# IoT_pro_01.net
KiCad netlist of a schematic drawn in EAGLE
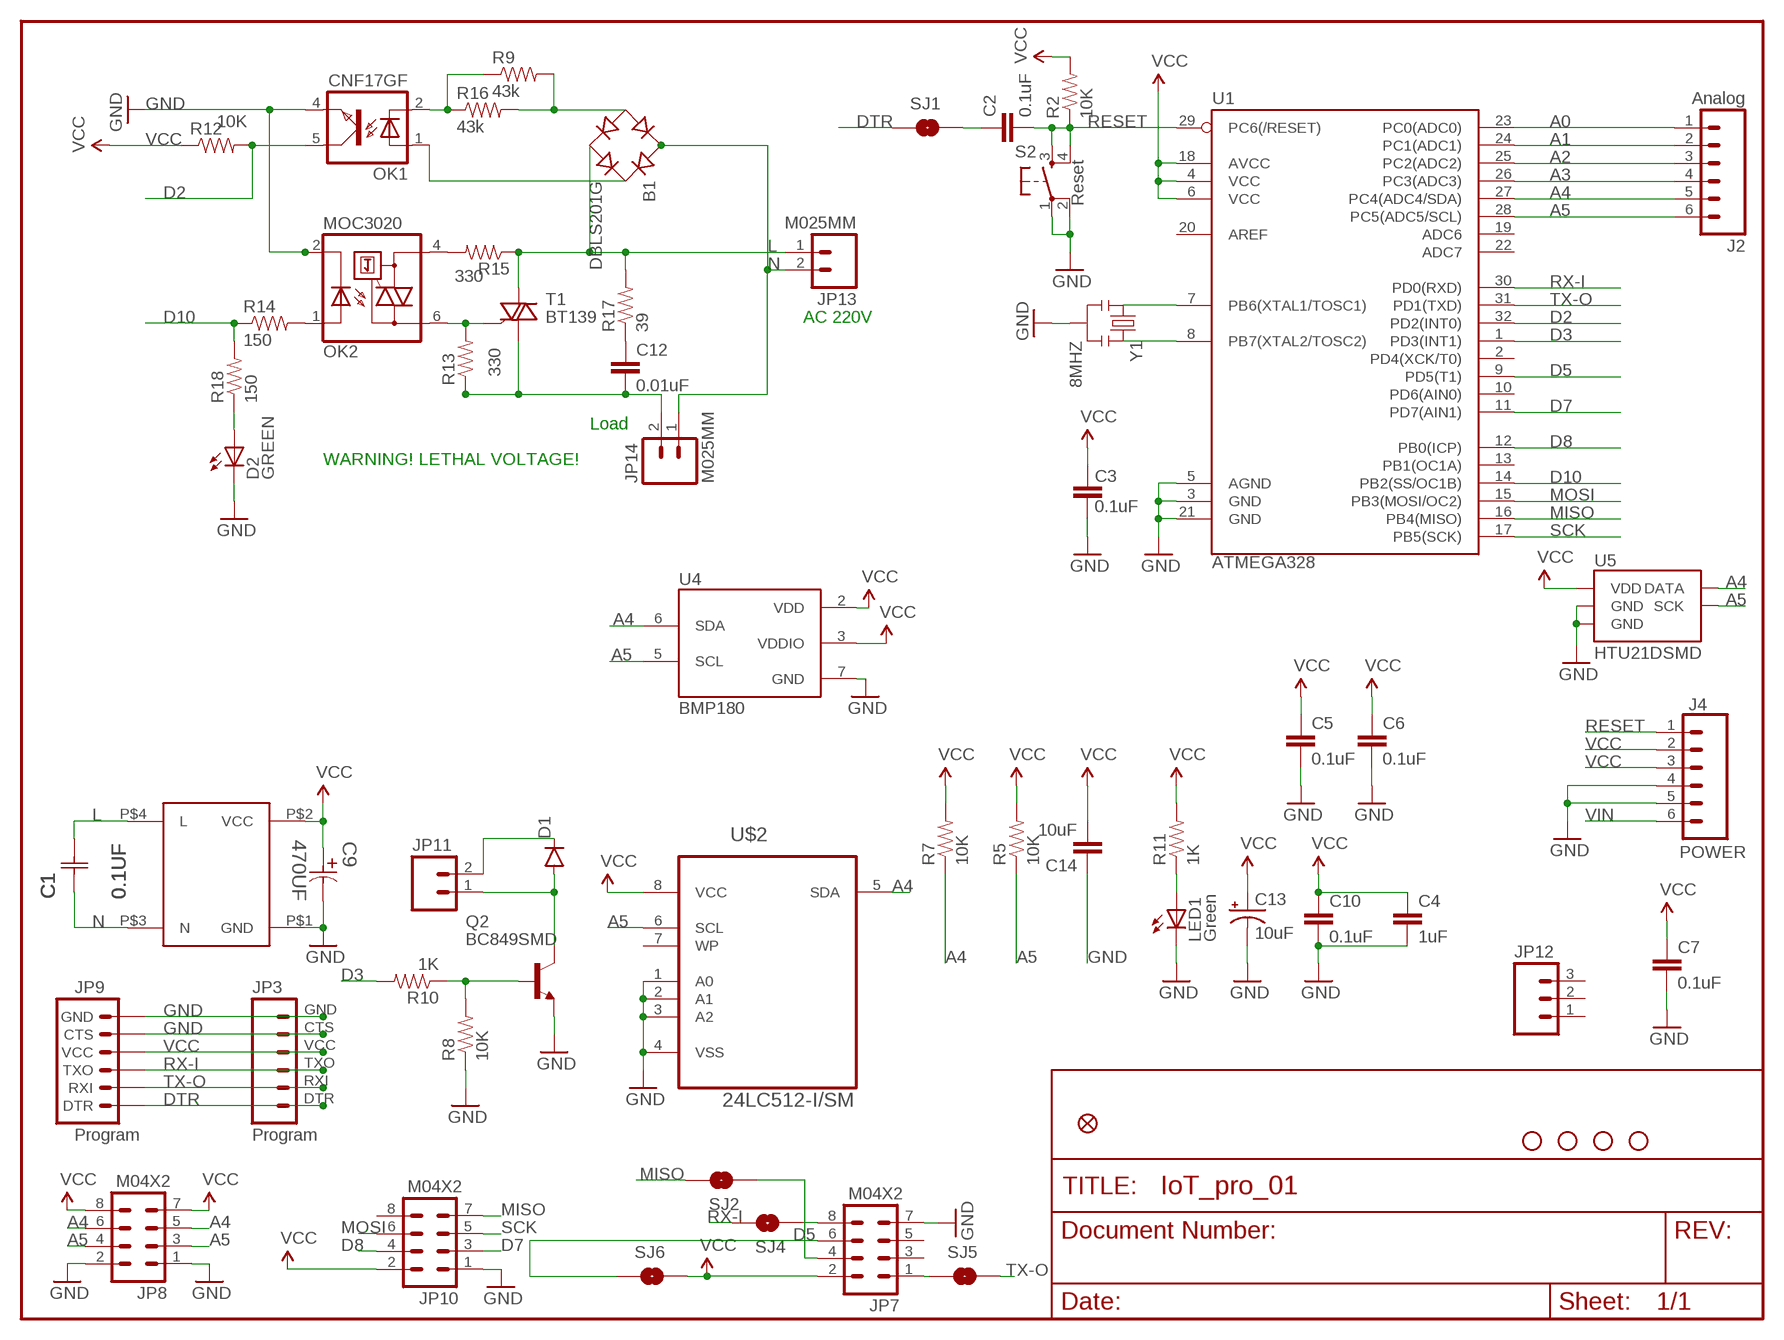
[diagram p0: schematic, sheet 1]

(export (version "E")
  (design (tool "Eeschema 10.0.6"))
  (components
    (comp (ref "B1")
      (value "DBLS201G")
      (footprint "eagle-import:DBS")
      (libsource (lib "eagle-import") (part "DB?GLS201"))
    )
    (comp (ref "C1")
      (value "0.1UF")
      (footprint "eagle-import:CAPM1750X500X1250")
      (fields (field (name "MPN") "ECQUAAF104M") (field (name "TOLERANCE") "±20%"))
      (libsource (lib "eagle-import") (part "ECQ-L17.5-T5UAAF104M"))
    )
    (comp (ref "C2")
      (value "0.1uF")
      (footprint "eagle-import:0805")
      (libsource (lib "eagle-import") (part "CAP0805"))
    )
    (comp (ref "C3")
      (value "0.1uF")
      (footprint "eagle-import:0805")
      (libsource (lib "eagle-import") (part "CAP0805"))
    )
    (comp (ref "C4")
      (value "1uF")
      (footprint "eagle-import:0805")
      (libsource (lib "eagle-import") (part "CAP0805"))
    )
    (comp (ref "C5")
      (value "0.1uF")
      (footprint "eagle-import:0805")
      (libsource (lib "eagle-import") (part "CAP0805"))
    )
    (comp (ref "C6")
      (value "0.1uF")
      (footprint "eagle-import:0805")
      (libsource (lib "eagle-import") (part "CAP0805"))
    )
    (comp (ref "C7")
      (value "0.1uF")
      (footprint "eagle-import:0805")
      (libsource (lib "eagle-import") (part "CAP0805"))
    )
    (comp (ref "C9")
      (value "470UF")
      (footprint "eagle-import:CAPAE660X800N")
      (fields (field (name "MPN") "EEE-FTA471XAP") (field (name "TOLERANCE") "±20 %"))
      (libsource (lib "eagle-import") (part "EEE--CASE-D8FTA471XAP"))
    )
    (comp (ref "C10")
      (value "0.1uF")
      (footprint "eagle-import:0805")
      (libsource (lib "eagle-import") (part "CAP0805"))
    )
    (comp (ref "C12")
      (value "0.01uF")
      (footprint "eagle-import:C1206")
      (libsource (lib "eagle-import") (part "C-EUC1206"))
    )
    (comp (ref "C13")
      (value "10uF")
      (footprint "eagle-import:EIA3216")
      (libsource (lib "eagle-import") (part "CAP_POL1206"))
    )
    (comp (ref "C14")
      (value "10uF")
      (footprint "eagle-import:1206")
      (libsource (lib "eagle-import") (part "SparkFun-Capacitors_CAP1206"))
    )
    (comp (ref "D1")
      (value "DIODESOD")
      (footprint "eagle-import:SOD-323")
      (libsource (lib "eagle-import") (part "DIODESOD"))
    )
    (comp (ref "D2")
      (value "GREEN")
      (footprint "eagle-import:PLCC2")
      (libsource (lib "eagle-import") (part "_T679-?-1E1F1LG"))
    )
    (comp (ref "J2")
      (value "Analog")
      (footprint "eagle-import:1X06")
      (libsource (lib "eagle-import") (part "M06SIP"))
    )
    (comp (ref "J4")
      (value "POWER")
      (footprint "eagle-import:1X06")
      (libsource (lib "eagle-import") (part "M06SIP"))
    )
    (comp (ref "JP2")
      (value "FIDUCIAL1X2.5")
      (footprint "eagle-import:FIDUCIAL-1X2.5")
      (libsource (lib "eagle-import") (part "FIDUCIAL1X2.5"))
    )
    (comp (ref "JP3")
      (value "Program")
      (footprint "eagle-import:1X06")
      (libsource (lib "eagle-import") (part "SparkFun-Connectors_M06SIP"))
    )
    (comp (ref "JP7")
      (value "M04X2")
      (footprint "eagle-import:2X4")
      (libsource (lib "eagle-import") (part "M04X2"))
    )
    (comp (ref "JP8")
      (value "M04X2")
      (footprint "eagle-import:2X4")
      (libsource (lib "eagle-import") (part "M04X2"))
    )
    (comp (ref "JP9")
      (value "Program")
      (footprint "eagle-import:1X06-SMD")
      (libsource (lib "eagle-import") (part "ARDUINO_SERIAL_PROGRAMSMD"))
    )
    (comp (ref "JP10")
      (value "M04X2")
      (footprint "eagle-import:2X4")
      (libsource (lib "eagle-import") (part "M04X2"))
    )
    (comp (ref "JP11")
      (value "M02PTH")
      (footprint "eagle-import:1X02")
      (libsource (lib "eagle-import") (part "M02PTH"))
    )
    (comp (ref "JP12")
      (value "M03PTH")
      (footprint "eagle-import:1X03")
      (libsource (lib "eagle-import") (part "M03PTH"))
    )
    (comp (ref "JP13")
      (value "M025MM")
      (footprint "eagle-import:SCREWTERMINAL-5MM-2")
      (libsource (lib "eagle-import") (part "M025MM"))
    )
    (comp (ref "JP14")
      (value "M025MM")
      (footprint "eagle-import:SCREWTERMINAL-5MM-2")
      (libsource (lib "eagle-import") (part "M025MM"))
    )
    (comp (ref "LED1")
      (value "Green")
      (footprint "eagle-import:PLCC2")
      (libsource (lib "eagle-import") (part "_T679-?-1E1F1LG"))
    )
    (comp (ref "OK1")
      (value "CNF17GF")
      (footprint "eagle-import:DIL06B")
      (libsource (lib "eagle-import") (part "CNF17GF"))
    )
    (comp (ref "OK2")
      (value "MOC3020")
      (footprint "eagle-import:DIL6-SMD")
      (fields (field (name "MF") "FAIRCHILD SEMICONDUCTOR") (field (name "MPN") "MOC3031SM"))
      (libsource (lib "eagle-import") (part "MOC30S31"))
    )
    (comp (ref "Q2")
      (value "BC849SMD")
      (footprint "eagle-import:SOT23-BEC")
      (libsource (lib "eagle-import") (part "BC849SMD"))
    )
    (comp (ref "R2")
      (value "10K")
      (footprint "eagle-import:0805")
      (libsource (lib "eagle-import") (part "RESISTOR0805-RES"))
    )
    (comp (ref "R5")
      (value "10K")
      (footprint "eagle-import:0805")
      (libsource (lib "eagle-import") (part "RESISTOR0805-RES"))
    )
    (comp (ref "R7")
      (value "10K")
      (footprint "eagle-import:0805")
      (libsource (lib "eagle-import") (part "RESISTOR0805-RES"))
    )
    (comp (ref "R8")
      (value "10K")
      (footprint "eagle-import:0805")
      (libsource (lib "eagle-import") (part "RESISTOR0805-RES"))
    )
    (comp (ref "R9")
      (value "43k")
      (footprint "eagle-import:1206")
      (fields (field (name "K") "45K"))
      (libsource (lib "eagle-import") (part "SparkFun-Resistors_RESISTOR1206"))
    )
    (comp (ref "R10")
      (value "1K")
      (footprint "eagle-import:0805")
      (libsource (lib "eagle-import") (part "RESISTOR0805-RES"))
    )
    (comp (ref "R11")
      (value "1K")
      (footprint "eagle-import:0805")
      (libsource (lib "eagle-import") (part "RESISTOR0805-RES"))
    )
    (comp (ref "R12")
      (value "RESISTOR0805-RES")
      (footprint "eagle-import:0805")
      (fields (field (name "OHM") "10K"))
      (libsource (lib "eagle-import") (part "SparkFun-Resistors_RESISTOR0805-RES"))
    )
    (comp (ref "R13")
      (value "RESISTOR1206")
      (footprint "eagle-import:1206")
      (fields (field (name "OHM") "330"))
      (libsource (lib "eagle-import") (part "SparkFun-Resistors_RESISTOR1206"))
    )
    (comp (ref "R14")
      (value "150")
      (footprint "eagle-import:0805")
      (fields (field (name "OHM") "330"))
      (libsource (lib "eagle-import") (part "SparkFun-Resistors_RESISTOR0805-RES"))
    )
    (comp (ref "R15")
      (value "RESISTOR1206")
      (footprint "eagle-import:1206")
      (fields (field (name "OHM") "330"))
      (libsource (lib "eagle-import") (part "SparkFun-Resistors_RESISTOR1206"))
    )
    (comp (ref "R16")
      (value "43k")
      (footprint "eagle-import:1206")
      (fields (field (name "K") "45K"))
      (libsource (lib "eagle-import") (part "SparkFun-Resistors_RESISTOR1206"))
    )
    (comp (ref "R17")
      (value "39")
      (footprint "eagle-import:1206")
      (fields (field (name "K") "45K"))
      (libsource (lib "eagle-import") (part "SparkFun-Resistors_RESISTOR1206"))
    )
    (comp (ref "R18")
      (value "150")
      (footprint "eagle-import:0805")
      (fields (field (name "OHM") "330"))
      (libsource (lib "eagle-import") (part "SparkFun-Resistors_RESISTOR0805-RES"))
    )
    (comp (ref "S2")
      (value "Reset")
      (footprint "eagle-import:TACTILE_SWITCH_SMD")
      (libsource (lib "eagle-import") (part "TAC_SWITCHSMD"))
    )
    (comp (ref "SJ1")
      (value "SOLDERJUMPERNC2")
      (footprint "eagle-import:SJ_2S-NOTRACE")
      (libsource (lib "eagle-import") (part "SOLDERJUMPERNC2"))
    )
    (comp (ref "SJ2")
      (value "SOLDERJUMPERNC2")
      (footprint "eagle-import:SJ_2S-NOTRACE")
      (libsource (lib "eagle-import") (part "SOLDERJUMPERNC2"))
    )
    (comp (ref "SJ4")
      (value "SOLDERJUMPERNC2")
      (footprint "eagle-import:SJ_2S-NOTRACE")
      (libsource (lib "eagle-import") (part "SOLDERJUMPERNC2"))
    )
    (comp (ref "SJ5")
      (value "SOLDERJUMPERNC2")
      (footprint "eagle-import:SJ_2S-NOTRACE")
      (libsource (lib "eagle-import") (part "SOLDERJUMPERNC2"))
    )
    (comp (ref "SJ6")
      (value "SOLDERJUMPERNC2")
      (footprint "eagle-import:SJ_2S-NOTRACE")
      (libsource (lib "eagle-import") (part "SOLDERJUMPERNC2"))
    )
    (comp (ref "T1")
      (value "BT139")
      (footprint "eagle-import:TO220AB")
      (libsource (lib "eagle-import") (part "BT136"))
    )
    (comp (ref "U$1")
      (value "STAND-OFFTIGHT")
      (footprint "eagle-import:STAND-OFF-TIGHT")
      (libsource (lib "eagle-import") (part "STAND-OFFTIGHT"))
    )
    (comp (ref "U$2")
      (value "24LC512-I/SM")
      (footprint "eagle-import:SOIC127P794X203-8N")
      (libsource (lib "eagle-import") (part "24LC512-I/SM"))
    )
    (comp (ref "U$3")
      (value "STAND-OFFTIGHT")
      (footprint "eagle-import:STAND-OFF-TIGHT")
      (libsource (lib "eagle-import") (part "STAND-OFFTIGHT"))
    )
    (comp (ref "U$4")
      (value "AC-DCCON")
      (footprint "eagle-import:VTX-214-001-103")
      (libsource (lib "eagle-import") (part "AC-DCCON"))
    )
    (comp (ref "U$9")
      (value "STAND-OFFTIGHT")
      (footprint "eagle-import:STAND-OFF-TIGHT")
      (libsource (lib "eagle-import") (part "STAND-OFFTIGHT"))
    )
    (comp (ref "U$10")
      (value "STAND-OFFTIGHT")
      (footprint "eagle-import:STAND-OFF-TIGHT")
      (libsource (lib "eagle-import") (part "STAND-OFFTIGHT"))
    )
    (comp (ref "U1")
      (value "ATMEGA328")
      (footprint "eagle-import:TQFP32-08")
      (libsource (lib "eagle-import") (part "ATMEGA168"))
    )
    (comp (ref "U4")
      (value "BMP180")
      (footprint "eagle-import:BMP180")
      (libsource (lib "eagle-import") (part "BMP180"))
    )
    (comp (ref "U5")
      (value "HTU21DSMD")
      (footprint "eagle-import:HTU21D")
      (libsource (lib "eagle-import") (part "HTU21DSMD"))
    )
    (comp (ref "Y1")
      (value "8MHZ")
      (footprint "eagle-import:RESONATOR-SMD")
      (libsource (lib "eagle-import") (part "RESONATOR8MHZ"))
    )
  )
  (nets
    (net (code "1") (name "/A0") (class "Default")
      (node (ref "J2") (pin "1") (pinfunction "1_1") (pintype "passive"))
      (node (ref "U1") (pin "23") (pinfunction "PC0(ADC0)_23") (pintype "bidirectional"))
    )
    (net (code "2") (name "/A1") (class "Default")
      (node (ref "J2") (pin "2") (pinfunction "2_2") (pintype "passive"))
      (node (ref "U1") (pin "24") (pinfunction "PC1(ADC1)_24") (pintype "bidirectional"))
    )
    (net (code "3") (name "/A2") (class "Default")
      (node (ref "J2") (pin "3") (pinfunction "3_3") (pintype "passive"))
      (node (ref "U1") (pin "25") (pinfunction "PC2(ADC2)_25") (pintype "bidirectional"))
    )
    (net (code "4") (name "/A3") (class "Default")
      (node (ref "J2") (pin "4") (pinfunction "4_4") (pintype "passive"))
      (node (ref "U1") (pin "26") (pinfunction "PC3(ADC3)_26") (pintype "bidirectional"))
    )
    (net (code "5") (name "/A4") (class "Default")
      (node (ref "J2") (pin "5") (pinfunction "5_5") (pintype "passive"))
      (node (ref "JP8") (pin "5") (pinfunction "5_5") (pintype "passive"))
      (node (ref "JP8") (pin "6") (pinfunction "6_6") (pintype "passive"))
      (node (ref "R7") (pin "1") (pinfunction "1_1") (pintype "passive"))
      (node (ref "U$2") (pin "5") (pinfunction "SDA_5") (pintype "bidirectional"))
      (node (ref "U1") (pin "27") (pinfunction "PC4(ADC4/SDA)_27") (pintype "bidirectional"))
      (node (ref "U4") (pin "6") (pinfunction "SDA_6") (pintype "bidirectional"))
      (node (ref "U5") (pin "DATA") (pinfunction "DATA_DATA") (pintype "bidirectional"))
    )
    (net (code "6") (name "/A5") (class "Default")
      (node (ref "J2") (pin "6") (pinfunction "6_6") (pintype "passive"))
      (node (ref "JP8") (pin "3") (pinfunction "3_3") (pintype "passive"))
      (node (ref "JP8") (pin "4") (pinfunction "4_4") (pintype "passive"))
      (node (ref "R5") (pin "1") (pinfunction "1_1") (pintype "passive"))
      (node (ref "U$2") (pin "6") (pinfunction "SCL_6") (pintype "input"))
      (node (ref "U1") (pin "28") (pinfunction "PC5(ADC5/SCL)_28") (pintype "bidirectional"))
      (node (ref "U4") (pin "5") (pinfunction "SCL_5") (pintype "input"))
      (node (ref "U5") (pin "SCK") (pinfunction "SCK_SCK") (pintype "input"))
    )
    (net (code "7") (name "/D2") (class "Default")
      (node (ref "OK1") (pin "5") (pinfunction "COL_5") (pintype "passive"))
      (node (ref "R12") (pin "2") (pinfunction "2_2") (pintype "passive"))
      (node (ref "U1") (pin "32") (pinfunction "PD2(INT0)_32") (pintype "bidirectional"))
    )
    (net (code "8") (name "/D3") (class "Default")
      (node (ref "R10") (pin "2") (pinfunction "2_2") (pintype "passive"))
      (node (ref "U1") (pin "1") (pinfunction "PD3(INT1)_1") (pintype "bidirectional"))
    )
    (net (code "9") (name "/D5") (class "Default")
      (node (ref "JP7") (pin "6") (pinfunction "6_6") (pintype "passive"))
      (node (ref "SJ6") (pin "1") (pinfunction "1_1") (pintype "passive"))
      (node (ref "U1") (pin "9") (pinfunction "PD5(T1)_9") (pintype "bidirectional"))
    )
    (net (code "10") (name "/D7") (class "Default")
      (node (ref "JP10") (pin "3") (pinfunction "3_3") (pintype "passive"))
      (node (ref "U1") (pin "11") (pinfunction "PD7(AIN1)_11") (pintype "bidirectional"))
    )
    (net (code "11") (name "/D8") (class "Default")
      (node (ref "JP10") (pin "4") (pinfunction "4_4") (pintype "passive"))
      (node (ref "U1") (pin "12") (pinfunction "PB0(ICP)_12") (pintype "bidirectional"))
    )
    (net (code "12") (name "/D10") (class "Default")
      (node (ref "R14") (pin "1") (pinfunction "1_1") (pintype "passive"))
      (node (ref "R18") (pin "2") (pinfunction "2_2") (pintype "passive"))
      (node (ref "U1") (pin "14") (pinfunction "PB2(SS/OC1B)_14") (pintype "bidirectional"))
    )
    (net (code "13") (name "/DTR") (class "Default")
      (node (ref "JP3") (pin "DTR") (pinfunction "1_DTR") (pintype "passive"))
      (node (ref "JP9") (pin "1") (pinfunction "DTR_1") (pintype "passive"))
      (node (ref "SJ1") (pin "1") (pinfunction "1_1") (pintype "passive"))
    )
    (net (code "14") (name "/L") (class "Default")
      (node (ref "B1") (pin "AC2") (pinfunction "AC2_AC2") (pintype "passive"))
      (node (ref "C1") (pin "2") (pinfunction "2_2") (pintype "passive"))
      (node (ref "JP13") (pin "1") (pinfunction "1_1") (pintype "passive"))
      (node (ref "R15") (pin "1") (pinfunction "1_1") (pintype "passive"))
      (node (ref "R17") (pin "2") (pinfunction "2_2") (pintype "passive"))
      (node (ref "T1") (pin "2") (pinfunction "A2_2") (pintype "passive"))
      (node (ref "U$4") (pin "P$4") (pinfunction "L_P$4") (pintype "bidirectional"))
    )
    (net (code "15") (name "/MISO") (class "Default")
      (node (ref "JP10") (pin "7") (pinfunction "7_7") (pintype "passive"))
      (node (ref "SJ2") (pin "2") (pinfunction "2_2") (pintype "passive"))
      (node (ref "U1") (pin "16") (pinfunction "PB4(MISO)_16") (pintype "bidirectional"))
    )
    (net (code "16") (name "/MOSI") (class "Default")
      (node (ref "JP10") (pin "6") (pinfunction "6_6") (pintype "passive"))
      (node (ref "U1") (pin "15") (pinfunction "PB3(MOSI/OC2)_15") (pintype "bidirectional"))
    )
    (net (code "17") (name "/N") (class "Default")
      (node (ref "B1") (pin "AC1") (pinfunction "AC1_AC1") (pintype "passive"))
      (node (ref "C1") (pin "1") (pinfunction "1_1") (pintype "passive"))
      (node (ref "JP13") (pin "2") (pinfunction "2_2") (pintype "passive"))
      (node (ref "JP14") (pin "1") (pinfunction "1_1") (pintype "passive"))
      (node (ref "U$4") (pin "P$3") (pinfunction "N_P$3") (pintype "bidirectional"))
    )
    (net (code "18") (name "/RESET") (class "Default")
      (node (ref "C2") (pin "2") (pinfunction "2_2") (pintype "passive"))
      (node (ref "J4") (pin "1") (pinfunction "1_1") (pintype "passive"))
      (node (ref "R2") (pin "1") (pinfunction "1_1") (pintype "passive"))
      (node (ref "S2") (pin "3") (pinfunction "3_3") (pintype "passive"))
      (node (ref "S2") (pin "4") (pinfunction "4_4") (pintype "passive"))
      (node (ref "U1") (pin "29") (pinfunction "PC6(/RESET)_29") (pintype "bidirectional"))
    )
    (net (code "19") (name "/RX-I") (class "Default")
      (node (ref "JP3") (pin "TXO") (pinfunction "3_TXO") (pintype "passive"))
      (node (ref "JP9") (pin "3") (pinfunction "TXO_3") (pintype "passive"))
      (node (ref "SJ4") (pin "2") (pinfunction "2_2") (pintype "passive"))
      (node (ref "U1") (pin "30") (pinfunction "PD0(RXD)_30") (pintype "bidirectional"))
    )
    (net (code "20") (name "/SCK") (class "Default")
      (node (ref "JP10") (pin "5") (pinfunction "5_5") (pintype "passive"))
      (node (ref "U1") (pin "17") (pinfunction "PB5(SCK)_17") (pintype "bidirectional"))
    )
    (net (code "21") (name "/TX-O") (class "Default")
      (node (ref "JP3") (pin "RXI") (pinfunction "2_RXI") (pintype "passive"))
      (node (ref "JP9") (pin "2") (pinfunction "RXI_2") (pintype "passive"))
      (node (ref "SJ5") (pin "2") (pinfunction "2_2") (pintype "passive"))
      (node (ref "U1") (pin "31") (pinfunction "PD1(TXD)_31") (pintype "bidirectional"))
    )
    (net (code "22") (name "/VIN") (class "Default")
      (node (ref "J4") (pin "6") (pinfunction "6_6") (pintype "passive"))
    )
    (net (code "23") (name "GND") (class "Default")
      (node (ref "C10") (pin "2") (pinfunction "2_2") (pintype "passive"))
      (node (ref "C13") (pin "C") (pinfunction "-_C") (pintype "passive"))
      (node (ref "C14") (pin "1") (pinfunction "1_1") (pintype "passive"))
      (node (ref "C3") (pin "1") (pinfunction "1_1") (pintype "passive"))
      (node (ref "C4") (pin "2") (pinfunction "2_2") (pintype "passive"))
      (node (ref "C5") (pin "2") (pinfunction "2_2") (pintype "passive"))
      (node (ref "C6") (pin "2") (pinfunction "2_2") (pintype "passive"))
      (node (ref "C7") (pin "2") (pinfunction "2_2") (pintype "passive"))
      (node (ref "C9") (pin "2") (pinfunction "2_2") (pintype "passive"))
      (node (ref "D2") (pin "C") (pinfunction "C_C") (pintype "passive"))
      (node (ref "J4") (pin "4") (pinfunction "4_4") (pintype "passive"))
      (node (ref "J4") (pin "5") (pinfunction "5_5") (pintype "passive"))
      (node (ref "JP10") (pin "1") (pinfunction "1_1") (pintype "passive"))
      (node (ref "JP3") (pin "CTS") (pinfunction "5_CTS") (pintype "passive"))
      (node (ref "JP3") (pin "GND") (pinfunction "6_GND") (pintype "passive"))
      (node (ref "JP7") (pin "7") (pinfunction "7_7") (pintype "passive"))
      (node (ref "JP8") (pin "1") (pinfunction "1_1") (pintype "passive"))
      (node (ref "JP8") (pin "2") (pinfunction "2_2") (pintype "passive"))
      (node (ref "JP9") (pin "5") (pinfunction "CTS_5") (pintype "passive"))
      (node (ref "JP9") (pin "6") (pinfunction "GND_6") (pintype "passive"))
      (node (ref "LED1") (pin "C") (pinfunction "C_C") (pintype "passive"))
      (node (ref "OK1") (pin "4") (pinfunction "EMIT_4") (pintype "passive"))
      (node (ref "OK2") (pin "2") (pinfunction "C_2") (pintype "passive"))
      (node (ref "Q2") (pin "E") (pinfunction "E_E") (pintype "passive"))
      (node (ref "R8") (pin "1") (pinfunction "1_1") (pintype "passive"))
      (node (ref "S2") (pin "1") (pinfunction "1_1") (pintype "passive"))
      (node (ref "S2") (pin "2") (pinfunction "2_2") (pintype "passive"))
      (node (ref "U$2") (pin "1") (pinfunction "A0_1") (pintype "input"))
      (node (ref "U$2") (pin "2") (pinfunction "A1_2") (pintype "input"))
      (node (ref "U$2") (pin "3") (pinfunction "A2_3") (pintype "input"))
      (node (ref "U$2") (pin "4") (pinfunction "VSS_4") (pintype "passive"))
      (node (ref "U$4") (pin "P$1") (pinfunction "GND_P$1") (pintype "bidirectional"))
      (node (ref "U1") (pin "21") (pinfunction "GND_21") (pintype "bidirectional"))
      (node (ref "U1") (pin "3") (pinfunction "GND_3") (pintype "bidirectional"))
      (node (ref "U1") (pin "5") (pinfunction "AGND_5") (pintype "bidirectional"))
      (node (ref "U4") (pin "7") (pinfunction "GND_7") (pintype "power_in"))
      (node (ref "U5") (pin "7") (pinfunction "GND_7") (pintype "power_in"))
      (node (ref "U5") (pin "GND") (pinfunction "GND_GND") (pintype "power_in"))
      (node (ref "Y1") (pin "2") (pinfunction "2_2") (pintype "passive"))
    )
    (net (code "24") (name "Net-(B1-Pad-)") (class "Default")
      (node (ref "B1") (pin "-") (pinfunction "-_-") (pintype "passive"))
      (node (ref "R16") (pin "2") (pinfunction "2_2") (pintype "passive"))
      (node (ref "R9") (pin "2") (pinfunction "2_2") (pintype "passive"))
    )
    (net (code "25") (name "Net-(C2-Pad1)") (class "Default")
      (node (ref "C2") (pin "1") (pinfunction "1_1") (pintype "passive"))
      (node (ref "SJ1") (pin "2") (pinfunction "2_2") (pintype "passive"))
    )
    (net (code "26") (name "Net-(C12-Pad1)") (class "Default")
      (node (ref "C12") (pin "1") (pinfunction "1_1") (pintype "passive"))
      (node (ref "R17") (pin "1") (pinfunction "1_1") (pintype "passive"))
    )
    (net (code "27") (name "Net-(D1-PadA)") (class "Default")
      (node (ref "D1") (pin "A") (pinfunction "A_A") (pintype "passive"))
      (node (ref "JP11") (pin "1") (pinfunction "1_1") (pintype "passive"))
      (node (ref "Q2") (pin "C") (pinfunction "C_C") (pintype "passive"))
    )
    (net (code "28") (name "Net-(D1-PadC)") (class "Default")
      (node (ref "D1") (pin "C") (pinfunction "C_C") (pintype "passive"))
      (node (ref "JP11") (pin "2") (pinfunction "2_2") (pintype "passive"))
    )
    (net (code "29") (name "Net-(D2-PadA)") (class "Default")
      (node (ref "D2") (pin "A") (pinfunction "A_A") (pintype "passive"))
      (node (ref "R18") (pin "1") (pinfunction "1_1") (pintype "passive"))
    )
    (net (code "30") (name "Net-(JP7-Pad1)") (class "Default")
      (node (ref "JP7") (pin "1") (pinfunction "1_1") (pintype "passive"))
      (node (ref "SJ5") (pin "1") (pinfunction "1_1") (pintype "passive"))
    )
    (net (code "31") (name "Net-(JP7-Pad4)") (class "Default")
      (node (ref "JP7") (pin "4") (pinfunction "4_4") (pintype "passive"))
      (node (ref "SJ2") (pin "1") (pinfunction "1_1") (pintype "passive"))
    )
    (net (code "32") (name "Net-(JP7-Pad8)") (class "Default")
      (node (ref "JP7") (pin "8") (pinfunction "8_8") (pintype "passive"))
      (node (ref "SJ4") (pin "1") (pinfunction "1_1") (pintype "passive"))
    )
    (net (code "33") (name "Net-(LED1-PadA)") (class "Default")
      (node (ref "LED1") (pin "A") (pinfunction "A_A") (pintype "passive"))
      (node (ref "R11") (pin "1") (pinfunction "1_1") (pintype "passive"))
    )
    (net (code "34") (name "Net-(OK1-A)") (class "Default")
      (node (ref "B1") (pin "+") (pinfunction "+_+") (pintype "passive"))
      (node (ref "OK1") (pin "1") (pinfunction "A_1") (pintype "passive"))
    )
    (net (code "35") (name "Net-(OK1-C)") (class "Default")
      (node (ref "OK1") (pin "2") (pinfunction "C_2") (pintype "passive"))
      (node (ref "R16") (pin "1") (pinfunction "1_1") (pintype "passive"))
      (node (ref "R9") (pin "1") (pinfunction "1_1") (pintype "passive"))
    )
    (net (code "36") (name "Net-(OK2-A)") (class "Default")
      (node (ref "OK2") (pin "1") (pinfunction "A_1") (pintype "passive"))
      (node (ref "R14") (pin "2") (pinfunction "2_2") (pintype "passive"))
    )
    (net (code "37") (name "Net-(OK2-A1)") (class "Default")
      (node (ref "OK2") (pin "4") (pinfunction "A1_4") (pintype "passive"))
      (node (ref "R15") (pin "2") (pinfunction "2_2") (pintype "passive"))
    )
    (net (code "38") (name "Net-(OK2-A2)") (class "Default")
      (node (ref "OK2") (pin "6") (pinfunction "A2_6") (pintype "passive"))
      (node (ref "R13") (pin "2") (pinfunction "2_2") (pintype "passive"))
      (node (ref "T1") (pin "3") (pinfunction "G_3") (pintype "passive"))
    )
    (net (code "39") (name "Net-(Q2-PadB)") (class "Default")
      (node (ref "Q2") (pin "B") (pinfunction "B_B") (pintype "passive"))
      (node (ref "R10") (pin "1") (pinfunction "1_1") (pintype "passive"))
      (node (ref "R8") (pin "2") (pinfunction "2_2") (pintype "passive"))
    )
    (net (code "40") (name "Net-(T1-A1)") (class "Default")
      (node (ref "C12") (pin "2") (pinfunction "2_2") (pintype "passive"))
      (node (ref "JP14") (pin "2") (pinfunction "2_2") (pintype "passive"))
      (node (ref "R13") (pin "1") (pinfunction "1_1") (pintype "passive"))
      (node (ref "T1") (pin "1") (pinfunction "A1_1") (pintype "passive"))
    )
    (net (code "41") (name "Net-(U1-PB6(XTAL1{slash}TOSC1))") (class "Default")
      (node (ref "U1") (pin "7") (pinfunction "PB6(XTAL1/TOSC1)_7") (pintype "bidirectional"))
      (node (ref "Y1") (pin "1") (pinfunction "1_1") (pintype "passive"))
    )
    (net (code "42") (name "Net-(U1-PB7(XTAL2{slash}TOSC2))") (class "Default")
      (node (ref "U1") (pin "8") (pinfunction "PB7(XTAL2/TOSC2)_8") (pintype "bidirectional"))
      (node (ref "Y1") (pin "3") (pinfunction "3_3") (pintype "passive"))
    )
    (net (code "43") (name "VCC") (class "Default")
      (node (ref "C10") (pin "1") (pinfunction "1_1") (pintype "passive"))
      (node (ref "C13") (pin "A") (pinfunction "+_A") (pintype "passive"))
      (node (ref "C14") (pin "2") (pinfunction "2_2") (pintype "passive"))
      (node (ref "C3") (pin "2") (pinfunction "2_2") (pintype "passive"))
      (node (ref "C4") (pin "1") (pinfunction "1_1") (pintype "passive"))
      (node (ref "C5") (pin "1") (pinfunction "1_1") (pintype "passive"))
      (node (ref "C6") (pin "1") (pinfunction "1_1") (pintype "passive"))
      (node (ref "C7") (pin "1") (pinfunction "1_1") (pintype "passive"))
      (node (ref "C9") (pin "1") (pinfunction "1_1") (pintype "passive"))
      (node (ref "J4") (pin "2") (pinfunction "2_2") (pintype "passive"))
      (node (ref "J4") (pin "3") (pinfunction "3_3") (pintype "passive"))
      (node (ref "JP10") (pin "2") (pinfunction "2_2") (pintype "passive"))
      (node (ref "JP3") (pin "VCC") (pinfunction "4_VCC") (pintype "passive"))
      (node (ref "JP7") (pin "2") (pinfunction "2_2") (pintype "passive"))
      (node (ref "JP8") (pin "7") (pinfunction "7_7") (pintype "passive"))
      (node (ref "JP8") (pin "8") (pinfunction "8_8") (pintype "passive"))
      (node (ref "JP9") (pin "4") (pinfunction "VCC_4") (pintype "passive"))
      (node (ref "R11") (pin "2") (pinfunction "2_2") (pintype "passive"))
      (node (ref "R12") (pin "1") (pinfunction "1_1") (pintype "passive"))
      (node (ref "R2") (pin "2") (pinfunction "2_2") (pintype "passive"))
      (node (ref "R5") (pin "2") (pinfunction "2_2") (pintype "passive"))
      (node (ref "R7") (pin "2") (pinfunction "2_2") (pintype "passive"))
      (node (ref "SJ6") (pin "2") (pinfunction "2_2") (pintype "passive"))
      (node (ref "U$2") (pin "8") (pinfunction "VCC_8") (pintype "power_in"))
      (node (ref "U$4") (pin "P$2") (pinfunction "VCC_P$2") (pintype "bidirectional"))
      (node (ref "U1") (pin "18") (pinfunction "AVCC_18") (pintype "bidirectional"))
      (node (ref "U1") (pin "4") (pinfunction "VCC_4") (pintype "bidirectional"))
      (node (ref "U1") (pin "6") (pinfunction "VCC_6") (pintype "bidirectional"))
      (node (ref "U4") (pin "2") (pinfunction "VDD_2") (pintype "power_in"))
      (node (ref "U4") (pin "3") (pinfunction "VDDIO_3") (pintype "power_in"))
      (node (ref "U5") (pin "VDD") (pinfunction "VDD_VDD") (pintype "power_in"))
    )
    (net (code "44") (name "unconnected-(JP7-Pad3)") (class "Default")
      (node (ref "JP7") (pin "3") (pinfunction "3_3") (pintype "passive"))
    )
    (net (code "45") (name "unconnected-(JP7-Pad5)") (class "Default")
      (node (ref "JP7") (pin "5") (pinfunction "5_5") (pintype "passive"))
    )
    (net (code "46") (name "unconnected-(JP10-Pad8)") (class "Default")
      (node (ref "JP10") (pin "8") (pinfunction "8_8") (pintype "passive"))
    )
    (net (code "47") (name "unconnected-(JP12-Pad1)") (class "Default")
      (node (ref "JP12") (pin "1") (pinfunction "1_1") (pintype "passive"))
    )
    (net (code "48") (name "unconnected-(JP12-Pad2)") (class "Default")
      (node (ref "JP12") (pin "2") (pinfunction "2_2") (pintype "passive"))
    )
    (net (code "49") (name "unconnected-(JP12-Pad3)") (class "Default")
      (node (ref "JP12") (pin "3") (pinfunction "3_3") (pintype "passive"))
    )
    (net (code "50") (name "unconnected-(U$2-WP-Pad7)") (class "Default")
      (node (ref "U$2") (pin "7") (pinfunction "WP_7") (pintype "input"))
    )
    (net (code "51") (name "unconnected-(U1-ADC6-Pad19)") (class "Default")
      (node (ref "U1") (pin "19") (pinfunction "ADC6_19") (pintype "bidirectional"))
    )
    (net (code "52") (name "unconnected-(U1-ADC7-Pad22)") (class "Default")
      (node (ref "U1") (pin "22") (pinfunction "ADC7_22") (pintype "bidirectional"))
    )
    (net (code "53") (name "unconnected-(U1-AREF-Pad20)") (class "Default")
      (node (ref "U1") (pin "20") (pinfunction "AREF_20") (pintype "bidirectional"))
    )
    (net (code "54") (name "unconnected-(U1-PB1(OC1A)-Pad13)") (class "Default")
      (node (ref "U1") (pin "13") (pinfunction "PB1(OC1A)_13") (pintype "bidirectional"))
    )
    (net (code "55") (name "unconnected-(U1-PD4(XCK{slash}T0)-Pad2)") (class "Default")
      (node (ref "U1") (pin "2") (pinfunction "PD4(XCK/T0)_2") (pintype "bidirectional"))
    )
    (net (code "56") (name "unconnected-(U1-PD6(AIN0)-Pad10)") (class "Default")
      (node (ref "U1") (pin "10") (pinfunction "PD6(AIN0)_10") (pintype "bidirectional"))
    )
  )
)
